# mutteruhr-Haus.net
KiCad netlist of a schematic drawn in EAGLE
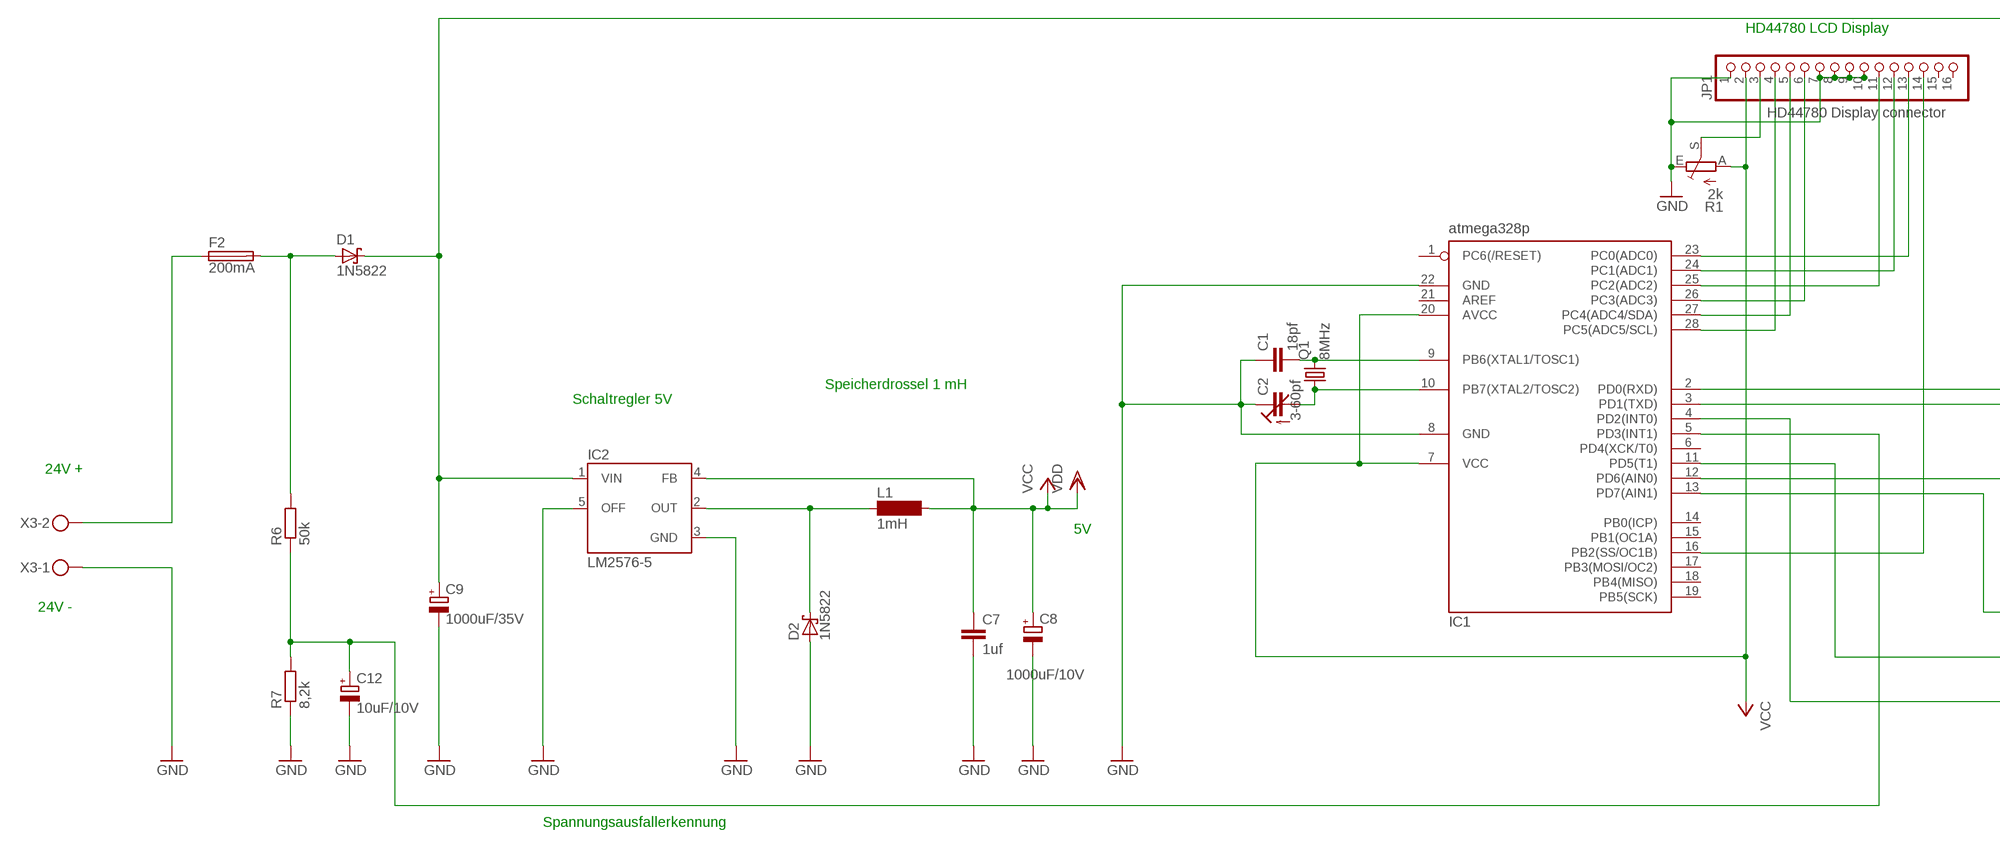
[diagram p0: schematic, sheet 1, part 1 of 2]
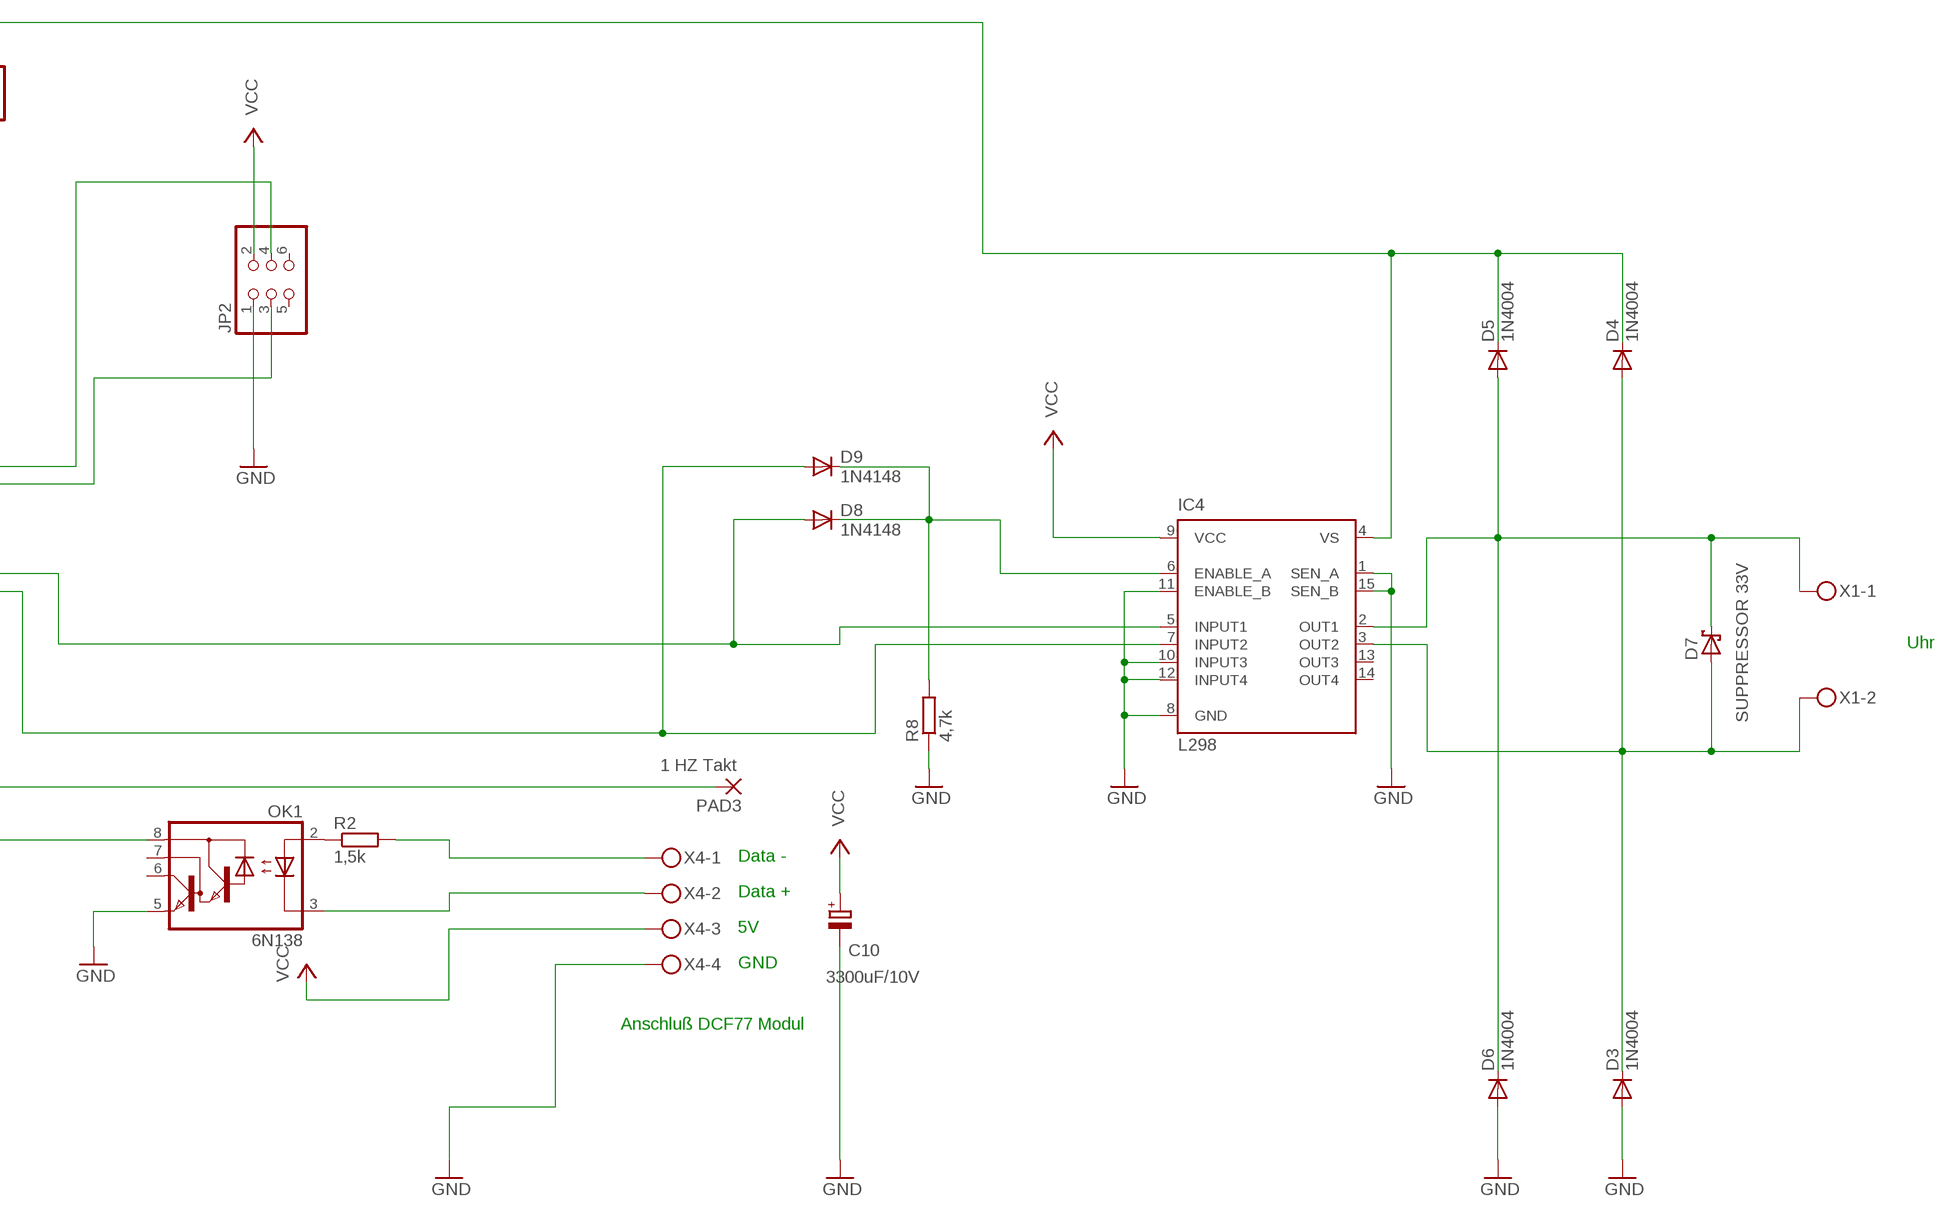
[diagram p1: schematic, sheet 1, part 2 of 2]

(export (version "E")
  (design (tool "Eeschema 10.0.6"))
  (components
    (comp (ref "C1")
      (value "18pf")
      (footprint "eagle-import:C050-024X044")
      (libsource (lib "eagle-import") (part "C-EU050-024X044"))
    )
    (comp (ref "C2")
      (value "3-60pf")
      (footprint "eagle-import:CTRIM3050.505")
      (libsource (lib "eagle-import") (part "C-TRIMM3050.505"))
    )
    (comp (ref "C7")
      (value "1uf")
      (footprint "eagle-import:C5B5.5")
      (libsource (lib "eagle-import") (part "C5/5.5"))
    )
    (comp (ref "C8")
      (value "1000uF/10V")
      (footprint "eagle-import:E5-8,5")
      (libsource (lib "eagle-import") (part "CPOL-EUE5-8.5"))
    )
    (comp (ref "C9")
      (value "1000uF/35V")
      (footprint "eagle-import:E5-8,5")
      (libsource (lib "eagle-import") (part "CPOL-EUE5-8.5"))
    )
    (comp (ref "C10")
      (value "3300uF/10V")
      (footprint "eagle-import:E7,5-16")
      (libsource (lib "eagle-import") (part "CPOL-EUE7.5-16"))
    )
    (comp (ref "C12")
      (value "10uF/10V")
      (footprint "eagle-import:E5-5")
      (libsource (lib "eagle-import") (part "rcl-2_CPOL-EUE5-5"))
    )
    (comp (ref "D1")
      (value "1N5822")
      (footprint "eagle-import:DO41-7.6")
      (libsource (lib "eagle-import") (part "1N5819-B"))
    )
    (comp (ref "D2")
      (value "1N5822")
      (footprint "eagle-import:DO41-7.6")
      (libsource (lib "eagle-import") (part "1N5819-B"))
    )
    (comp (ref "D3")
      (value "1N4004")
      (footprint "eagle-import:DO41-10")
      (libsource (lib "eagle-import") (part "1N4004"))
    )
    (comp (ref "D4")
      (value "1N4004")
      (footprint "eagle-import:DO41-10")
      (libsource (lib "eagle-import") (part "1N4004"))
    )
    (comp (ref "D5")
      (value "1N4004")
      (footprint "eagle-import:DO41-10")
      (libsource (lib "eagle-import") (part "1N4004"))
    )
    (comp (ref "D6")
      (value "1N4004")
      (footprint "eagle-import:DO41-10")
      (libsource (lib "eagle-import") (part "1N4004"))
    )
    (comp (ref "D7")
      (value "SUPPRESSOR 33V")
      (footprint "eagle-import:DO41-10")
      (libsource (lib "eagle-import") (part "P4KEXX"))
    )
    (comp (ref "D8")
      (value "1N4148")
      (footprint "eagle-import:DO35-7")
      (libsource (lib "eagle-import") (part "1N4148DO35-7"))
    )
    (comp (ref "D9")
      (value "1N4148")
      (footprint "eagle-import:DO35-7")
      (libsource (lib "eagle-import") (part "1N4148DO35-7"))
    )
    (comp (ref "F2")
      (value "200mA")
      (footprint "eagle-import:SH25")
      (fields (field (name "MF") "SCHURTER") (field (name "MPN") "0031.8211"))
      (libsource (lib "eagle-import") (part "SH25"))
    )
    (comp (ref "IC1")
      (value "atmega328p")
      (footprint "eagle-import:DIL28-3")
      (libsource (lib "eagle-import") (part "MEGA8-P"))
    )
    (comp (ref "IC2")
      (value "LM2576-5")
      (footprint "eagle-import:TO220-5")
      (libsource (lib "eagle-import") (part "LM2576T"))
    )
    (comp (ref "IC4")
      (value "L298")
      (footprint "eagle-import:MULTIWATT-15")
      (fields (field (name "MPN") "L298N"))
      (libsource (lib "eagle-import") (part "L298"))
    )
    (comp (ref "JP1")
      (value "HD44780 Display connector")
      (footprint "eagle-import:1X16")
      (libsource (lib "eagle-import") (part "PINHD-1X16_2.54"))
    )
    (comp (ref "JP2")
      (value "PINHD-2X3")
      (footprint "eagle-import:2X03")
      (libsource (lib "eagle-import") (part "PINHD-2X3"))
    )
    (comp (ref "L1")
      (value "1mH")
      (footprint "eagle-import:BS11")
      (libsource (lib "eagle-import") (part "BS11"))
    )
    (comp (ref "OK1")
      (value "6N138")
      (footprint "eagle-import:DIL08")
      (fields (field (name "MF") "VISHAY/TELEFUNKEN"))
      (libsource (lib "eagle-import") (part "6N138"))
    )
    (comp (ref "PAD3")
      (value "1 HZ Takt")
      (footprint "eagle-import:2,54_0,8")
      (libsource (lib "eagle-import") (part "2,54/0,8"))
    )
    (comp (ref "Q1")
      (value "8MHz")
      (footprint "eagle-import:HC18U-V")
      (libsource (lib "eagle-import") (part "CRYSTALHC18U-V"))
    )
    (comp (ref "R1")
      (value "2k")
      (footprint "eagle-import:RS3")
      (libsource (lib "eagle-import") (part "TRIM_EU-RS3"))
    )
    (comp (ref "R2")
      (value "1,5k")
      (footprint "eagle-import:0207_10")
      (libsource (lib "eagle-import") (part "R-EU_0207/10"))
    )
    (comp (ref "R6")
      (value "50k")
      (footprint "eagle-import:0207_10")
      (libsource (lib "eagle-import") (part "R-EU_0207/10"))
    )
    (comp (ref "R7")
      (value "8,2k")
      (footprint "eagle-import:0207_10")
      (libsource (lib "eagle-import") (part "R-EU_0207/10"))
    )
    (comp (ref "R8")
      (value "4,7k")
      (footprint "eagle-import:0207_10")
      (libsource (lib "eagle-import") (part "R-EU_0207/10"))
    )
    (comp (ref "X1")
      (value "MKDSN1,5/2-5,08")
      (footprint "eagle-import:MKDSN1,5_2-5,08")
      (fields (field (name "MPN") "MKDSN 1,5/2-5.08"))
      (libsource (lib "eagle-import") (part "MKDSN1,5/2-5,08"))
    )
    (comp (ref "X3")
      (value "MKDSN1,5/2-5,08")
      (footprint "eagle-import:MKDSN1,5_2-5,08")
      (fields (field (name "MPN") "MKDSN 1,5/2-5.08"))
      (libsource (lib "eagle-import") (part "MKDSN1,5/2-5,08"))
    )
    (comp (ref "X4")
      (value "MKDSN1,5/4-5,08")
      (footprint "eagle-import:MKDSN1,5_4-5,08")
      (fields (field (name "MPN") "SMKDSN1,5/4-5,08"))
      (libsource (lib "eagle-import") (part "MKDSN1,5/4-5,08"))
    )
  )
  (nets
    (net (code "1") (name "GND") (class "Default")
      (node (ref "C1") (pin "1") (pinfunction "1_1") (pintype "passive"))
      (node (ref "C10") (pin "-") (pinfunction "-_-") (pintype "passive"))
      (node (ref "C12") (pin "-") (pinfunction "-_-") (pintype "passive"))
      (node (ref "C2") (pin "1") (pinfunction "E_1") (pintype "passive"))
      (node (ref "C7") (pin "2") (pinfunction "2_2") (pintype "passive"))
      (node (ref "C8") (pin "-") (pinfunction "-_-") (pintype "passive"))
      (node (ref "C9") (pin "-") (pinfunction "-_-") (pintype "passive"))
      (node (ref "D2") (pin "A") (pinfunction "A_A") (pintype "passive"))
      (node (ref "D3") (pin "A") (pinfunction "A_A") (pintype "passive"))
      (node (ref "D6") (pin "A") (pinfunction "A_A") (pintype "passive"))
      (node (ref "IC1") (pin "22") (pinfunction "GND_22") (pintype "power_in"))
      (node (ref "IC1") (pin "8") (pinfunction "GND_8") (pintype "power_in"))
      (node (ref "IC2") (pin "3") (pinfunction "GND_3") (pintype "power_in"))
      (node (ref "IC2") (pin "5") (pinfunction "OFF_5") (pintype "input"))
      (node (ref "IC4") (pin "1") (pinfunction "SEN_A_1") (pintype "input"))
      (node (ref "IC4") (pin "10") (pinfunction "INPUT3_10") (pintype "input"))
      (node (ref "IC4") (pin "11") (pinfunction "ENABLE_B_11") (pintype "input"))
      (node (ref "IC4") (pin "12") (pinfunction "INPUT4_12") (pintype "input"))
      (node (ref "IC4") (pin "15") (pinfunction "SEN_B_15") (pintype "input"))
      (node (ref "IC4") (pin "8") (pinfunction "GND_8") (pintype "power_in"))
      (node (ref "JP1") (pin "1") (pinfunction "1_1") (pintype "passive"))
      (node (ref "JP1") (pin "10") (pinfunction "10_10") (pintype "passive"))
      (node (ref "JP1") (pin "7") (pinfunction "7_7") (pintype "passive"))
      (node (ref "JP1") (pin "8") (pinfunction "8_8") (pintype "passive"))
      (node (ref "JP1") (pin "9") (pinfunction "9_9") (pintype "passive"))
      (node (ref "JP2") (pin "1") (pinfunction "1_1") (pintype "passive"))
      (node (ref "OK1") (pin "5") (pinfunction "GND_5") (pintype "passive"))
      (node (ref "R1") (pin "E") (pinfunction "E_E") (pintype "passive"))
      (node (ref "R7") (pin "1") (pinfunction "1_1") (pintype "passive"))
      (node (ref "R8") (pin "1") (pinfunction "1_1") (pintype "passive"))
      (node (ref "X3") (pin "1") (pinfunction "KL_1") (pintype "passive"))
      (node (ref "X4") (pin "4") (pinfunction "KL_4") (pintype "passive"))
    )
    (net (code "2") (name "Net-(C2-A)") (class "Default")
      (node (ref "C2") (pin "2") (pinfunction "A_2") (pintype "passive"))
      (node (ref "IC1") (pin "10") (pinfunction "PB7(XTAL2/TOSC2)_10") (pintype "bidirectional"))
      (node (ref "Q1") (pin "1") (pinfunction "1_1") (pintype "passive"))
    )
    (net (code "3") (name "Net-(D1-PadA)") (class "Default")
      (node (ref "D1") (pin "A") (pinfunction "A_A") (pintype "passive"))
      (node (ref "F2") (pin "2") (pinfunction "2_2") (pintype "passive"))
      (node (ref "R6") (pin "2") (pinfunction "2_2") (pintype "passive"))
    )
    (net (code "4") (name "Net-(IC1-PB2(SS{slash}OC1B))") (class "Default")
      (node (ref "IC1") (pin "16") (pinfunction "PB2(SS/OC1B)_16") (pintype "bidirectional"))
      (node (ref "JP1") (pin "14") (pinfunction "14_14") (pintype "passive"))
    )
    (net (code "5") (name "Net-(IC1-PB6(XTAL1{slash}TOSC1))") (class "Default")
      (node (ref "C1") (pin "2") (pinfunction "2_2") (pintype "passive"))
      (node (ref "IC1") (pin "9") (pinfunction "PB6(XTAL1/TOSC1)_9") (pintype "bidirectional"))
      (node (ref "Q1") (pin "2") (pinfunction "2_2") (pintype "passive"))
    )
    (net (code "6") (name "Net-(IC1-PC0(ADC0))") (class "Default")
      (node (ref "IC1") (pin "23") (pinfunction "PC0(ADC0)_23") (pintype "bidirectional"))
      (node (ref "JP1") (pin "13") (pinfunction "13_13") (pintype "passive"))
    )
    (net (code "7") (name "Net-(IC1-PC1(ADC1))") (class "Default")
      (node (ref "IC1") (pin "24") (pinfunction "PC1(ADC1)_24") (pintype "bidirectional"))
      (node (ref "JP1") (pin "12") (pinfunction "12_12") (pintype "passive"))
    )
    (net (code "8") (name "Net-(IC1-PC2(ADC2))") (class "Default")
      (node (ref "IC1") (pin "25") (pinfunction "PC2(ADC2)_25") (pintype "bidirectional"))
      (node (ref "JP1") (pin "11") (pinfunction "11_11") (pintype "passive"))
    )
    (net (code "9") (name "Net-(IC1-PC3(ADC3))") (class "Default")
      (node (ref "IC1") (pin "26") (pinfunction "PC3(ADC3)_26") (pintype "bidirectional"))
      (node (ref "JP1") (pin "6") (pinfunction "6_6") (pintype "passive"))
    )
    (net (code "10") (name "Net-(IC1-PC4(ADC4{slash}SDA))") (class "Default")
      (node (ref "IC1") (pin "27") (pinfunction "PC4(ADC4/SDA)_27") (pintype "bidirectional"))
      (node (ref "JP1") (pin "5") (pinfunction "5_5") (pintype "passive"))
    )
    (net (code "11") (name "Net-(IC1-PC5(ADC5{slash}SCL))") (class "Default")
      (node (ref "IC1") (pin "28") (pinfunction "PC5(ADC5/SCL)_28") (pintype "bidirectional"))
      (node (ref "JP1") (pin "4") (pinfunction "4_4") (pintype "passive"))
    )
    (net (code "12") (name "Net-(IC1-PD0(RXD))") (class "Default")
      (node (ref "IC1") (pin "2") (pinfunction "PD0(RXD)_2") (pintype "bidirectional"))
      (node (ref "JP2") (pin "4") (pinfunction "4_4") (pintype "passive"))
    )
    (net (code "13") (name "Net-(IC1-PD1(TXD))") (class "Default")
      (node (ref "IC1") (pin "3") (pinfunction "PD1(TXD)_3") (pintype "bidirectional"))
      (node (ref "JP2") (pin "3") (pinfunction "3_3") (pintype "passive"))
    )
    (net (code "14") (name "Net-(IC1-PD2(INT0))") (class "Default")
      (node (ref "IC1") (pin "4") (pinfunction "PD2(INT0)_4") (pintype "bidirectional"))
      (node (ref "OK1") (pin "8") (pinfunction "VCC_8") (pintype "passive"))
    )
    (net (code "15") (name "Net-(IC1-PD3(INT1))") (class "Default")
      (node (ref "C12") (pin "+") (pinfunction "+_+") (pintype "passive"))
      (node (ref "IC1") (pin "5") (pinfunction "PD3(INT1)_5") (pintype "bidirectional"))
      (node (ref "R6") (pin "1") (pinfunction "1_1") (pintype "passive"))
      (node (ref "R7") (pin "2") (pinfunction "2_2") (pintype "passive"))
    )
    (net (code "16") (name "Net-(IC1-PD5(T1))") (class "Default")
      (node (ref "IC1") (pin "11") (pinfunction "PD5(T1)_11") (pintype "bidirectional"))
      (node (ref "PAD3") (pin "1") (pinfunction "P_1") (pintype "passive"))
    )
    (net (code "17") (name "Net-(IC1-PD6(AIN0))") (class "Default")
      (node (ref "D8") (pin "A") (pinfunction "A_A") (pintype "passive"))
      (node (ref "IC1") (pin "12") (pinfunction "PD6(AIN0)_12") (pintype "bidirectional"))
      (node (ref "IC4") (pin "5") (pinfunction "INPUT1_5") (pintype "input"))
    )
    (net (code "18") (name "Net-(IC1-PD7(AIN1))") (class "Default")
      (node (ref "D9") (pin "A") (pinfunction "A_A") (pintype "passive"))
      (node (ref "IC1") (pin "13") (pinfunction "PD7(AIN1)_13") (pintype "bidirectional"))
      (node (ref "IC4") (pin "7") (pinfunction "INPUT2_7") (pintype "input"))
    )
    (net (code "19") (name "Net-(IC2-OUT)") (class "Default")
      (node (ref "D2") (pin "C") (pinfunction "C_C") (pintype "passive"))
      (node (ref "IC2") (pin "2") (pinfunction "OUT_2") (pintype "output"))
      (node (ref "L1") (pin "1") (pinfunction "1_1") (pintype "passive"))
    )
    (net (code "20") (name "Net-(IC2-VIN)") (class "Default")
      (node (ref "C9") (pin "+") (pinfunction "+_+") (pintype "passive"))
      (node (ref "D1") (pin "C") (pinfunction "C_C") (pintype "passive"))
      (node (ref "D4") (pin "C") (pinfunction "C_C") (pintype "passive"))
      (node (ref "D5") (pin "C") (pinfunction "C_C") (pintype "passive"))
      (node (ref "IC2") (pin "1") (pinfunction "VIN_1") (pintype "power_in"))
      (node (ref "IC4") (pin "4") (pinfunction "VS_4") (pintype "power_in"))
    )
    (net (code "21") (name "Net-(IC4-ENABLE_A)") (class "Default")
      (node (ref "D8") (pin "C") (pinfunction "C_C") (pintype "passive"))
      (node (ref "D9") (pin "C") (pinfunction "C_C") (pintype "passive"))
      (node (ref "IC4") (pin "6") (pinfunction "ENABLE_A_6") (pintype "input"))
      (node (ref "R8") (pin "2") (pinfunction "2_2") (pintype "passive"))
    )
    (net (code "22") (name "Net-(IC4-OUT1)") (class "Default")
      (node (ref "D5") (pin "A") (pinfunction "A_A") (pintype "passive"))
      (node (ref "D6") (pin "C") (pinfunction "C_C") (pintype "passive"))
      (node (ref "D7") (pin "C") (pinfunction "C_C") (pintype "passive"))
      (node (ref "IC4") (pin "2") (pinfunction "OUT1_2") (pintype "output"))
      (node (ref "X1") (pin "1") (pinfunction "KL_1") (pintype "passive"))
    )
    (net (code "23") (name "Net-(IC4-OUT2)") (class "Default")
      (node (ref "D3") (pin "C") (pinfunction "C_C") (pintype "passive"))
      (node (ref "D4") (pin "A") (pinfunction "A_A") (pintype "passive"))
      (node (ref "D7") (pin "A") (pinfunction "A_A") (pintype "passive"))
      (node (ref "IC4") (pin "3") (pinfunction "OUT2_3") (pintype "output"))
      (node (ref "X1") (pin "2") (pinfunction "KL_2") (pintype "passive"))
    )
    (net (code "24") (name "Net-(JP1-Pad3)") (class "Default")
      (node (ref "JP1") (pin "3") (pinfunction "3_3") (pintype "passive"))
      (node (ref "R1") (pin "S") (pinfunction "S_S") (pintype "passive"))
    )
    (net (code "25") (name "Net-(OK1-A)") (class "Default")
      (node (ref "OK1") (pin "2") (pinfunction "A_2") (pintype "passive"))
      (node (ref "R2") (pin "1") (pinfunction "1_1") (pintype "passive"))
    )
    (net (code "26") (name "Net-(OK1-C)") (class "Default")
      (node (ref "OK1") (pin "3") (pinfunction "C_3") (pintype "passive"))
      (node (ref "X4") (pin "2") (pinfunction "KL_2") (pintype "passive"))
    )
    (net (code "27") (name "Net-(X3B-KL)") (class "Default")
      (node (ref "F2") (pin "1") (pinfunction "1_1") (pintype "passive"))
      (node (ref "X3") (pin "2") (pinfunction "KL_2") (pintype "passive"))
    )
    (net (code "28") (name "Net-(X4A-KL)") (class "Default")
      (node (ref "R2") (pin "2") (pinfunction "2_2") (pintype "passive"))
      (node (ref "X4") (pin "1") (pinfunction "KL_1") (pintype "passive"))
    )
    (net (code "29") (name "VCC") (class "Default")
      (node (ref "C10") (pin "+") (pinfunction "+_+") (pintype "passive"))
      (node (ref "C7") (pin "1") (pinfunction "1_1") (pintype "passive"))
      (node (ref "C8") (pin "+") (pinfunction "+_+") (pintype "passive"))
      (node (ref "IC1") (pin "20") (pinfunction "AVCC_20") (pintype "power_in"))
      (node (ref "IC1") (pin "7") (pinfunction "VCC_7") (pintype "power_in"))
      (node (ref "IC2") (pin "4") (pinfunction "FB_4") (pintype "input"))
      (node (ref "IC4") (pin "9") (pinfunction "VCC_9") (pintype "power_in"))
      (node (ref "JP1") (pin "2") (pinfunction "2_2") (pintype "passive"))
      (node (ref "JP2") (pin "2") (pinfunction "2_2") (pintype "passive"))
      (node (ref "L1") (pin "2") (pinfunction "2_2") (pintype "passive"))
      (node (ref "R1") (pin "A") (pinfunction "A_A") (pintype "passive"))
      (node (ref "X4") (pin "3") (pinfunction "KL_3") (pintype "passive"))
    )
    (net (code "30") (name "unconnected-(IC1-AREF-Pad21)") (class "Default")
      (node (ref "IC1") (pin "21") (pinfunction "AREF_21") (pintype "passive"))
    )
    (net (code "31") (name "unconnected-(IC1-PB0(ICP)-Pad14)") (class "Default")
      (node (ref "IC1") (pin "14") (pinfunction "PB0(ICP)_14") (pintype "bidirectional"))
    )
    (net (code "32") (name "unconnected-(IC1-PB1(OC1A)-Pad15)") (class "Default")
      (node (ref "IC1") (pin "15") (pinfunction "PB1(OC1A)_15") (pintype "bidirectional"))
    )
    (net (code "33") (name "unconnected-(IC1-PB3(MOSI{slash}OC2)-Pad17)") (class "Default")
      (node (ref "IC1") (pin "17") (pinfunction "PB3(MOSI/OC2)_17") (pintype "bidirectional"))
    )
    (net (code "34") (name "unconnected-(IC1-PB4(MISO)-Pad18)") (class "Default")
      (node (ref "IC1") (pin "18") (pinfunction "PB4(MISO)_18") (pintype "bidirectional"))
    )
    (net (code "35") (name "unconnected-(IC1-PB5(SCK)-Pad19)") (class "Default")
      (node (ref "IC1") (pin "19") (pinfunction "PB5(SCK)_19") (pintype "bidirectional"))
    )
    (net (code "36") (name "unconnected-(IC1-PC6({slash}RESET)-Pad1)") (class "Default")
      (node (ref "IC1") (pin "1") (pinfunction "PC6(/RESET)_1") (pintype "bidirectional"))
    )
    (net (code "37") (name "unconnected-(IC1-PD4(XCK{slash}T0)-Pad6)") (class "Default")
      (node (ref "IC1") (pin "6") (pinfunction "PD4(XCK/T0)_6") (pintype "bidirectional"))
    )
    (net (code "38") (name "unconnected-(IC4-OUT3-Pad13)") (class "Default")
      (node (ref "IC4") (pin "13") (pinfunction "OUT3_13") (pintype "output"))
    )
    (net (code "39") (name "unconnected-(IC4-OUT4-Pad14)") (class "Default")
      (node (ref "IC4") (pin "14") (pinfunction "OUT4_14") (pintype "output"))
    )
    (net (code "40") (name "unconnected-(JP1-Pad15)") (class "Default")
      (node (ref "JP1") (pin "15") (pinfunction "15_15") (pintype "passive"))
    )
    (net (code "41") (name "unconnected-(JP1-Pad16)") (class "Default")
      (node (ref "JP1") (pin "16") (pinfunction "16_16") (pintype "passive"))
    )
    (net (code "42") (name "unconnected-(JP2-Pad5)") (class "Default")
      (node (ref "JP2") (pin "5") (pinfunction "5_5") (pintype "passive"))
    )
    (net (code "43") (name "unconnected-(JP2-Pad6)") (class "Default")
      (node (ref "JP2") (pin "6") (pinfunction "6_6") (pintype "passive"))
    )
    (net (code "44") (name "unconnected-(OK1-VB-Pad7)") (class "Default")
      (node (ref "OK1") (pin "7") (pinfunction "VB_7") (pintype "passive"))
    )
    (net (code "45") (name "unconnected-(OK1-VO-Pad6)") (class "Default")
      (node (ref "OK1") (pin "6") (pinfunction "VO_6") (pintype "passive"))
    )
  )
)
